# Main.net
KiCad netlist of a schematic drawn in Altium Designer
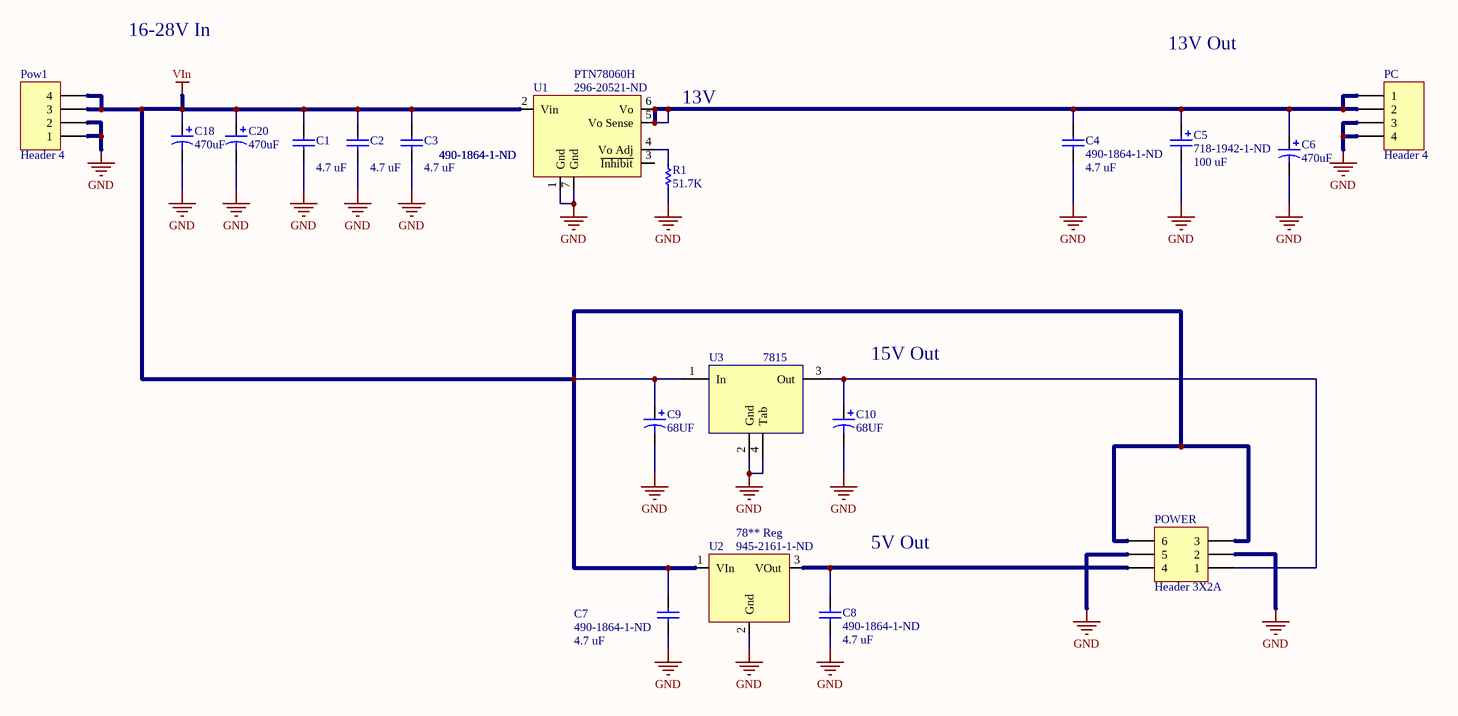
[diagram p0: Main.SchDoc]

(export (version "E")
  (design (tool "Eeschema 10.0.6"))
  (components
    (comp (ref "C1")
      (value "490-1864-1-ND")
      (footprint "1210C")
      (description "SMT Capacitor")
      (fields (field (name "ALTIUM_VALUE") "4.7 uF"))
      (libsource (lib "Miscellaneous Devices") (part "Capacitor - SMT"))
    )
    (comp (ref "C2")
      (value "490-1864-1-ND")
      (footprint "1210C")
      (description "SMT Capacitor")
      (fields (field (name "ALTIUM_VALUE") "4.7 uF"))
      (libsource (lib "Miscellaneous Devices") (part "Capacitor - SMT"))
    )
    (comp (ref "C3")
      (value "490-1864-1-ND")
      (footprint "1210C")
      (description "SMT Capacitor")
      (fields (field (name "ALTIUM_VALUE") "4.7 uF"))
      (libsource (lib "Miscellaneous Devices") (part "Capacitor - SMT"))
    )
    (comp (ref "C4")
      (value "490-1864-1-ND")
      (footprint "1210C")
      (description "SMT Capacitor")
      (fields (field (name "ALTIUM_VALUE") "4.7 uF"))
      (libsource (lib "Miscellaneous Devices") (part "Capacitor - SMT"))
    )
    (comp (ref "C5")
      (value "718-1942-1-ND")
      (footprint "F")
      (description "Polarized Capacitor (Radial)")
      (fields (field (name "ALTIUM_VALUE") "100 uF") (field (name "PUBLISHER") "Altium Limited"))
      (libsource (lib "") (part "Cap Pol1_1"))
    )
    (comp (ref "C6")
      (value "470uF")
      (footprint "CAPPR7.5-16x35")
      (description "Polarized Capacitor (Radial)")
      (fields (field (name "Comment") "Cap Pol1") (field (name "PUBLISHER") "Altium Limited"))
      (libsource (lib "Miscellaneous Devices") (part "Cap Pol1"))
    )
    (comp (ref "C7")
      (value "490-1864-1-ND")
      (footprint "1210C")
      (description "SMT Capacitor")
      (fields (field (name "ALTIUM_VALUE") "4.7 uF"))
      (libsource (lib "Miscellaneous Devices") (part "Capacitor - SMT"))
    )
    (comp (ref "C8")
      (value "490-1864-1-ND")
      (footprint "1210C")
      (description "SMT Capacitor")
      (fields (field (name "ALTIUM_VALUE") "4.7 uF"))
      (libsource (lib "Miscellaneous Devices") (part "Capacitor - SMT"))
    )
    (comp (ref "C9")
      (value "68UF")
      (footprint "V")
      (description "KEMET T520 KO-CAP  Polymer SMT Tantalum")
      (fields (field (name "VOLTAGE") "10V") (field (name "Comment") "Cap Pol3"))
      (libsource (lib "Miscellaneous Devices") (part "Cap Pol3"))
    )
    (comp (ref "C10")
      (value "68UF")
      (footprint "V")
      (description "KEMET T520 KO-CAP  Polymer SMT Tantalum")
      (fields (field (name "VOLTAGE") "10V") (field (name "Comment") "Cap Pol3"))
      (libsource (lib "Miscellaneous Devices") (part "Cap Pol3"))
    )
    (comp (ref "C18")
      (value "470uF")
      (footprint "CAPPR7.5-16x35")
      (description "Polarized Capacitor (Radial)")
      (fields (field (name "Comment") "Cap Pol1") (field (name "PUBLISHER") "Altium Limited"))
      (libsource (lib "Miscellaneous Devices") (part "Cap Pol1"))
    )
    (comp (ref "C20")
      (value "470uF")
      (footprint "CAPPR7.5-16x35")
      (description "Polarized Capacitor (Radial)")
      (fields (field (name "Comment") "Cap Pol1") (field (name "PUBLISHER") "Altium Limited"))
      (libsource (lib "Miscellaneous Devices") (part "Cap Pol1"))
    )
    (comp (ref "PC")
      (value "Header 4")
      (footprint "Molex Mini-Fit Jr 5569 - 4 Pin, RA, Flat")
      (description "Header, 4-Pin")
      (fields (field (name "PUBLISHER") "Altium Limited"))
      (libsource (lib "Miscellaneous Connectors") (part "Header 4"))
    )
    (comp (ref "Pow1")
      (value "Header 4")
      (footprint "Molex Mini-Fit Jr 5569 - 4 Pin, RA")
      (description "Header, 4-Pin")
      (fields (field (name "PUBLISHER") "Altium Limited"))
      (libsource (lib "") (part "Header 4_1"))
    )
    (comp (ref "POWER")
      (value "Header 3X2A")
      (footprint "Molex Mini-Fit Jr 5569 - 6 Pin, RA")
      (description "Header, 3-Pin, Dual row")
      (fields (field (name "PUBLISHER") "Altium Limited"))
      (libsource (lib "Miscellaneous Connectors") (part "Header 3X2A"))
    )
    (comp (ref "R1")
      (value "51.7K")
      (footprint "1206R")
      (description "Semiconductor Resistor")
      (fields (field (name "Comment") "Res Semi Small") (field (name "PUBLISHER") "Altium Limited"))
      (libsource (lib "Miscellaneous Devices") (part "Res Semi Small"))
    )
    (comp (ref "U1")
      (value "PTN78060H")
      (footprint "Ti Package EUC (R-PDSS-T7)")
      (description "3-A, WIDE-INPUT ADJUSTABLE SWITCHING REGULATOR")
      (fields (field (name "DKPN") "296-20521-ND"))
      (libsource (lib "Miscellaneous") (part "PTN78060H"))
    )
    (comp (ref "U2")
      (value "78** Reg")
      (footprint "R-78Txx-1.0/AC")
      (description "78** series Voltage Regulator")
      (fields (field (name "DKPN") "945-2161-1-ND"))
      (libsource (lib "ICs") (part "78** Voltage Regulator"))
    )
    (comp (ref "U3")
      (value "7815")
      (footprint "TO-220 - Small Heatsink")
      (description "1.2A Low-Dropout Voltage Regulator")
      (libsource (lib "ICs") (part "MIC2940"))
    )
  )
  (nets
    (net (code "1") (name "GND") (class "Default")
      (node (ref "C1") (pin "1") (pinfunction "1_1") (pintype "passive"))
      (node (ref "C10") (pin "2") (pinfunction "2_2") (pintype "passive"))
      (node (ref "C18") (pin "2") (pinfunction "2_2") (pintype "passive"))
      (node (ref "C2") (pin "1") (pinfunction "1_1") (pintype "passive"))
      (node (ref "C20") (pin "2") (pinfunction "2_2") (pintype "passive"))
      (node (ref "C3") (pin "1") (pinfunction "1_1") (pintype "passive"))
      (node (ref "C4") (pin "1") (pinfunction "1_1") (pintype "passive"))
      (node (ref "C5") (pin "2") (pinfunction "2_2") (pintype "passive"))
      (node (ref "C6") (pin "2") (pinfunction "2_2") (pintype "passive"))
      (node (ref "C7") (pin "1") (pinfunction "1_1") (pintype "passive"))
      (node (ref "C8") (pin "1") (pinfunction "1_1") (pintype "passive"))
      (node (ref "C9") (pin "2") (pinfunction "2_2") (pintype "passive"))
      (node (ref "PC") (pin "3") (pinfunction "3_3") (pintype "passive"))
      (node (ref "PC") (pin "4") (pinfunction "4_4") (pintype "passive"))
      (node (ref "POWER") (pin "2") (pinfunction "2_2") (pintype "passive"))
      (node (ref "POWER") (pin "5") (pinfunction "5_5") (pintype "passive"))
      (node (ref "Pow1") (pin "1") (pinfunction "1_1") (pintype "passive"))
      (node (ref "Pow1") (pin "2") (pinfunction "2_2") (pintype "passive"))
      (node (ref "R1") (pin "1") (pinfunction "1_1") (pintype "passive"))
      (node (ref "U1") (pin "1") (pinfunction "Gnd_1") (pintype "power_in"))
      (node (ref "U1") (pin "7") (pinfunction "Gnd_7") (pintype "power_in"))
      (node (ref "U2") (pin "2") (pinfunction "Gnd_2") (pintype "power_in"))
      (node (ref "U3") (pin "2") (pinfunction "Gnd_2") (pintype "power_in"))
      (node (ref "U3") (pin "4") (pinfunction "Tab_4") (pintype "power_in"))
    )
    (net (code "2") (name "Net-(U1-Vo)") (class "Default")
      (node (ref "C4") (pin "2") (pinfunction "2_2") (pintype "passive"))
      (node (ref "C5") (pin "1") (pinfunction "1_1") (pintype "passive"))
      (node (ref "C6") (pin "1") (pinfunction "1_1") (pintype "passive"))
      (node (ref "PC") (pin "1") (pinfunction "1_1") (pintype "passive"))
      (node (ref "PC") (pin "2") (pinfunction "2_2") (pintype "passive"))
      (node (ref "U1") (pin "5") (pinfunction "Vo_Sense_5") (pintype "power_in"))
      (node (ref "U1") (pin "6") (pinfunction "Vo_6") (pintype "power_in"))
    )
    (net (code "3") (name "Net-(U1-Vo_Adj)") (class "Default")
      (node (ref "R1") (pin "2") (pinfunction "2_2") (pintype "passive"))
      (node (ref "U1") (pin "4") (pinfunction "Vo_Adj_4") (pintype "passive"))
    )
    (net (code "4") (name "Net-(U2-VOut)") (class "Default")
      (node (ref "C8") (pin "2") (pinfunction "2_2") (pintype "passive"))
      (node (ref "POWER") (pin "4") (pinfunction "4_4") (pintype "passive"))
      (node (ref "U2") (pin "3") (pinfunction "VOut_3") (pintype "power_in"))
    )
    (net (code "5") (name "Net-(U3-Out)") (class "Default")
      (node (ref "C10") (pin "1") (pinfunction "1_1") (pintype "passive"))
      (node (ref "POWER") (pin "1") (pinfunction "1_1") (pintype "passive"))
      (node (ref "U3") (pin "3") (pinfunction "Out_3") (pintype "power_in"))
    )
    (net (code "6") (name "VIn") (class "Default")
      (node (ref "C1") (pin "2") (pinfunction "2_2") (pintype "passive"))
      (node (ref "C18") (pin "1") (pinfunction "1_1") (pintype "passive"))
      (node (ref "C2") (pin "2") (pinfunction "2_2") (pintype "passive"))
      (node (ref "C20") (pin "1") (pinfunction "1_1") (pintype "passive"))
      (node (ref "C3") (pin "2") (pinfunction "2_2") (pintype "passive"))
      (node (ref "C7") (pin "2") (pinfunction "2_2") (pintype "passive"))
      (node (ref "C9") (pin "1") (pinfunction "1_1") (pintype "passive"))
      (node (ref "POWER") (pin "3") (pinfunction "3_3") (pintype "passive"))
      (node (ref "POWER") (pin "6") (pinfunction "6_6") (pintype "passive"))
      (node (ref "Pow1") (pin "3") (pinfunction "3_3") (pintype "passive"))
      (node (ref "Pow1") (pin "4") (pinfunction "4_4") (pintype "passive"))
      (node (ref "U1") (pin "2") (pinfunction "Vin_2") (pintype "power_in"))
      (node (ref "U2") (pin "1") (pinfunction "VIn_1") (pintype "power_in"))
      (node (ref "U3") (pin "1") (pinfunction "In_1") (pintype "power_in"))
    )
    (net (code "7") (name "unconnected-(U1-Inhibit-Pad3)") (class "Default")
      (node (ref "U1") (pin "3") (pinfunction "Inhibit_3") (pintype "passive"))
    )
  )
)
